# MODULE_WIFI_LAMP_CONTROL.net
KiCad netlist of a schematic drawn in Altium Designer
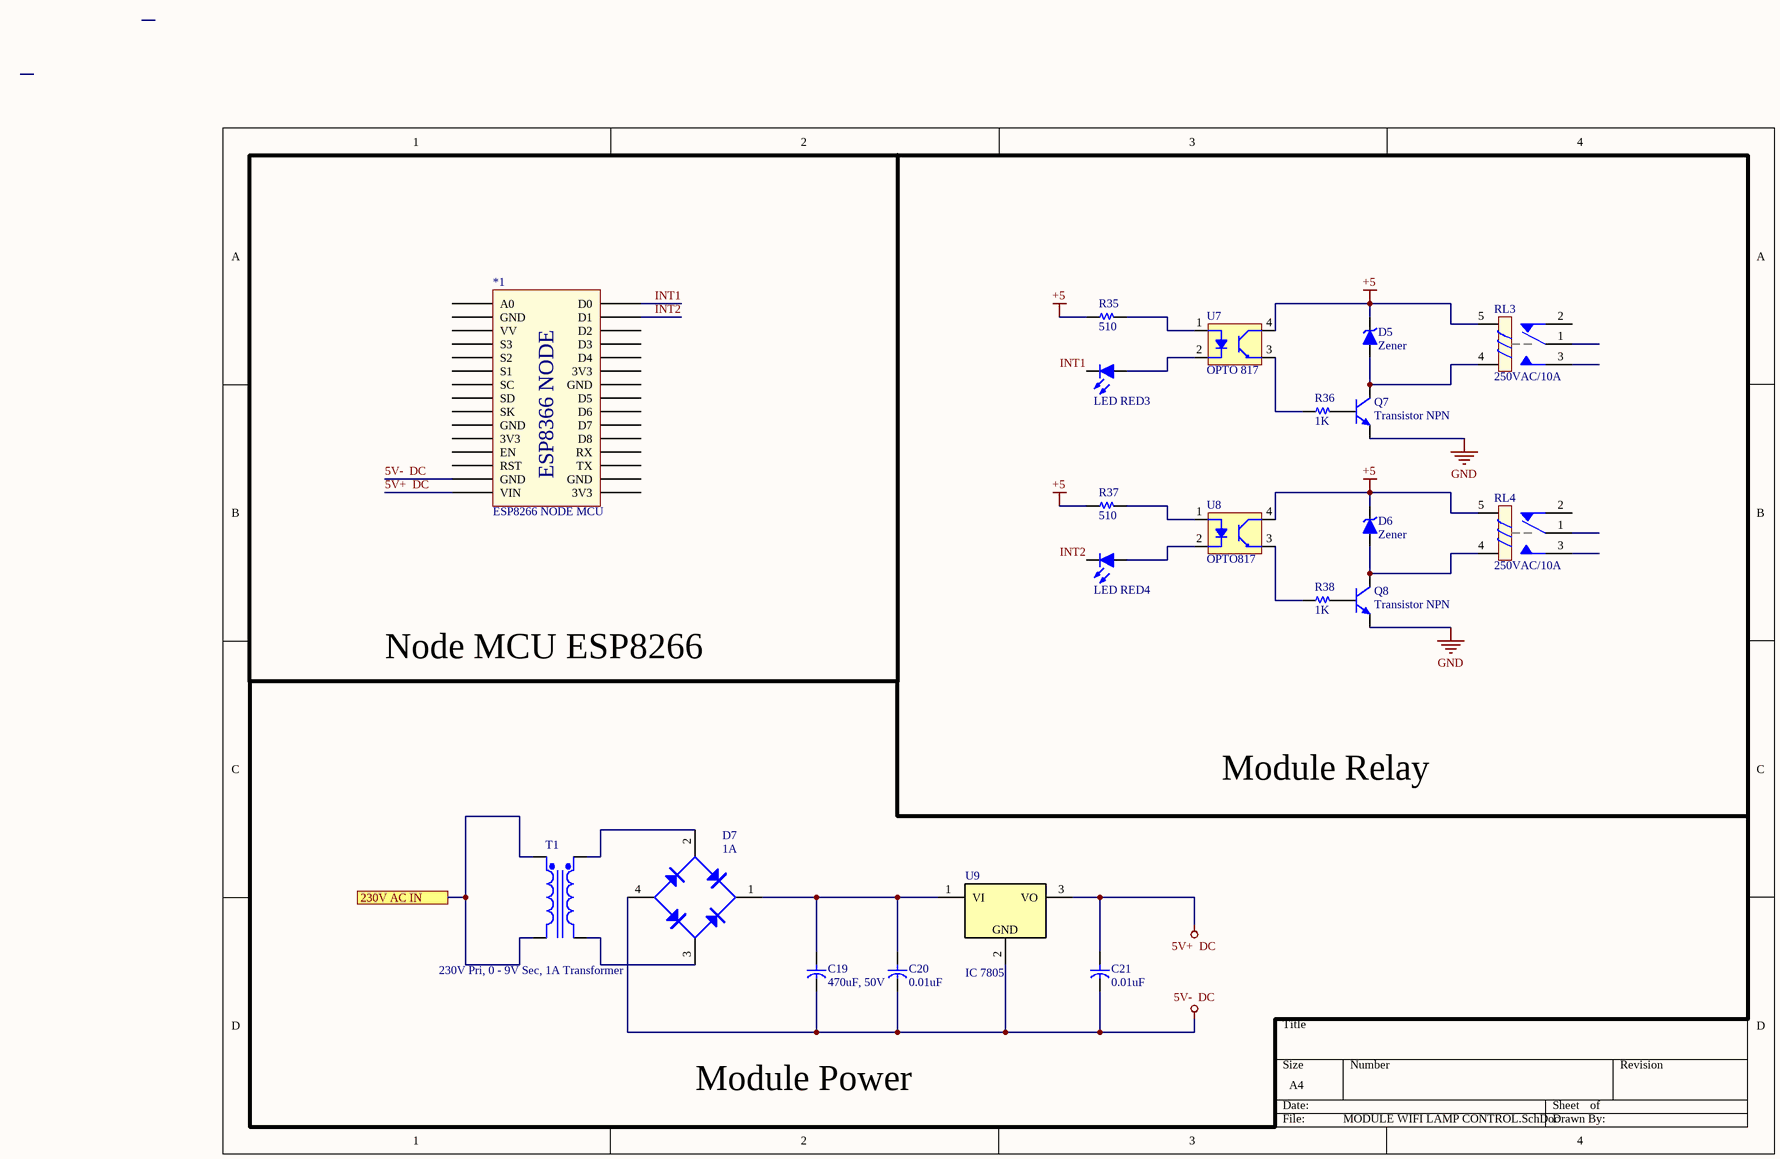
[diagram p0: MODULE WIFI LAMP CONTROL.SchDoc]

(export (version "E")
  (design (tool "Eeschema 10.0.6"))
  (components
    (comp (ref "*1")
      (value "ESP8266 NODE MCU")
      (footprint "ESP8266 NODE MCU")
      (libsource (lib "Altium_Lib_by_KhueNguyenCreator") (part "ESP8266 NODE MCU"))
    )
    (comp (ref "C19")
      (value "470uF, 50V")
      (footprint "CYL/D.500/LS.200")
      (description "Capacitor pol")
      (libsource (lib "chipfc_altium_libs") (part "Capacitor"))
    )
    (comp (ref "C20")
      (value "0.01uF")
      (footprint "CYL/D.500/LS.200")
      (description "Capacitor pol")
      (libsource (lib "chipfc_altium_libs") (part "Capacitor"))
    )
    (comp (ref "C21")
      (value "0.01uF")
      (footprint "CYL/D.500/LS.200")
      (description "Capacitor pol")
      (libsource (lib "chipfc_altium_libs") (part "Capacitor"))
    )
    (comp (ref "D5")
      (value "Zener")
      (footprint "DO-41")
      (description "Zener Diode")
      (libsource (lib "chipfc_altium_libs") (part "Diode Zener"))
    )
    (comp (ref "D6")
      (value "Zener")
      (footprint "DO-41")
      (description "Zener Diode")
      (libsource (lib "chipfc_altium_libs") (part "Diode Zener"))
    )
    (comp (ref "D7")
      (value "1A")
      (footprint "BRIDGE_DAN")
      (description "Diode Bridge")
      (libsource (lib "Devzone_SCHLib") (part "BRIDGE1"))
    )
    (comp (ref "LED RED3")
      (value "LED RED")
      (footprint "LED 5MM - RED")
      (description "Typical LED")
      (libsource (lib "chipfc_altium_libs") (part "Led"))
    )
    (comp (ref "LED RED4")
      (value "LED RED")
      (footprint "LED 5MM - RED")
      (description "Typical LED")
      (libsource (lib "chipfc_altium_libs") (part "Led"))
    )
    (comp (ref "Q7")
      (value "Transistor NPN")
      (footprint "SOT-23")
      (description "NPN Bipolar Transistor")
      (libsource (lib "chipfc_altium_libs") (part "Transistor NPN"))
    )
    (comp (ref "Q8")
      (value "Transistor NPN")
      (footprint "SOT-23")
      (description "NPN Bipolar Transistor")
      (libsource (lib "chipfc_altium_libs") (part "Transistor NPN"))
    )
    (comp (ref "R35")
      (value "510")
      (footprint "R 1/4W/300")
      (description "Resistor")
      (libsource (lib "chipfc_altium_libs") (part "Resistor"))
    )
    (comp (ref "R36")
      (value "1K")
      (footprint "R 1/4W/300")
      (description "Resistor")
      (libsource (lib "chipfc_altium_libs") (part "Resistor"))
    )
    (comp (ref "R37")
      (value "510")
      (footprint "R 1/4W/300")
      (description "Resistor")
      (libsource (lib "chipfc_altium_libs") (part "Resistor"))
    )
    (comp (ref "R38")
      (value "1K")
      (footprint "R 1/4W/300")
      (description "Resistor")
      (libsource (lib "chipfc_altium_libs") (part "Resistor"))
    )
    (comp (ref "RL3")
      (value "250VAC/10A")
      (footprint "Relay 5 Chan SRD")
      (description "Relay 5 Chan")
      (libsource (lib "Altium_Lib_by_KhueNguyenCreator") (part "Relay 5 Chan SRD"))
    )
    (comp (ref "RL4")
      (value "250VAC/10A")
      (footprint "Relay 5 Chan SRD")
      (description "Relay 5 Chan")
      (libsource (lib "Altium_Lib_by_KhueNguyenCreator") (part "Relay 5 Chan SRD"))
    )
    (comp (ref "T1")
      (value "230V Pri, 0 - 9V Sec, 1A Transformer")
      (footprint "TRF_4")
      (description "Transformer (Coupled Inductor Model)")
      (fields (field (name "PUBLISHER") "Altium Limited"))
      (libsource (lib "SCH_MyLib_0") (part "Trans Cupl"))
    )
    (comp (ref "U7")
      (value "OPTO 817")
      (footprint "DIP4 - PC817")
      (description "Opto PC817B")
      (libsource (lib "chipfc_altium_libs") (part "PC817"))
    )
    (comp (ref "U8")
      (value "OPTO817")
      (footprint "DIP4 - PC817")
      (description "Opto PC817B")
      (libsource (lib "chipfc_altium_libs") (part "PC817"))
    )
    (comp (ref "U9")
      (value "IC 7805")
      (footprint "DPAK_118_446_112X59_SMD")
      (description "Linear Voltage Regulator IC 1 Output 1.5A DPAK")
      (fields (field (name "MANUFACTURER") "Diodes") (field (name "MANUFACTURER PART NUMBER") "L7805CDT-TR"))
      (libsource (lib "Altium_Lib_by_KhueNguyenCreator") (part "REG_35V_5V-1.5A-7.5W-DPAK"))
    )
  )
  (nets
    (net (code "1") (name "+5") (class "Default")
      (node (ref "D5") (pin "2") (pinfunction "K_2") (pintype "passive"))
      (node (ref "D6") (pin "2") (pinfunction "K_2") (pintype "passive"))
      (node (ref "R35") (pin "1") (pinfunction "1_1") (pintype "passive"))
      (node (ref "R37") (pin "1") (pinfunction "1_1") (pintype "passive"))
      (node (ref "RL3") (pin "5") (pinfunction "5_5") (pintype "passive"))
      (node (ref "RL4") (pin "5") (pinfunction "5_5") (pintype "passive"))
      (node (ref "U7") (pin "4") (pinfunction "C_4") (pintype "passive"))
      (node (ref "U8") (pin "4") (pinfunction "C_4") (pintype "passive"))
    )
    (net (code "2") (name "/230V AC IN") (class "Default")
      (node (ref "T1") (pin "1") (pinfunction "Pri+_1") (pintype "passive"))
      (node (ref "T1") (pin "2") (pinfunction "Pri-_2") (pintype "passive"))
    )
    (net (code "3") (name "/INT1") (class "Default")
      (node (ref "*1") (pin "30") (pinfunction "D0_30") (pintype "passive"))
    )
    (net (code "4") (name "/INT2") (class "Default")
      (node (ref "*1") (pin "29") (pinfunction "D1_29") (pintype "passive"))
    )
    (net (code "5") (name "5V+  DC") (class "Default")
      (node (ref "*1") (pin "15") (pinfunction "VIN_15") (pintype "passive"))
      (node (ref "C21") (pin "1") (pinfunction "1_1") (pintype "passive"))
      (node (ref "U9") (pin "3") (pinfunction "VO_3") (pintype "passive"))
    )
    (net (code "6") (name "5V-  DC") (class "Default")
      (node (ref "*1") (pin "14") (pinfunction "GND_14") (pintype "passive"))
      (node (ref "C19") (pin "2") (pinfunction "2_2") (pintype "passive"))
      (node (ref "C20") (pin "2") (pinfunction "2_2") (pintype "passive"))
      (node (ref "C21") (pin "2") (pinfunction "2_2") (pintype "passive"))
      (node (ref "D7") (pin "4") (pinfunction "V-_4") (pintype "passive"))
      (node (ref "U9") (pin "2") (pintype "passive"))
    )
    (net (code "7") (name "GND") (class "Default")
      (node (ref "Q7") (pin "2") (pinfunction "E_2") (pintype "passive"))
      (node (ref "Q8") (pin "2") (pinfunction "E_2") (pintype "passive"))
    )
    (net (code "8") (name "Net-(D5-A)") (class "Default")
      (node (ref "D5") (pin "1") (pinfunction "A_1") (pintype "passive"))
      (node (ref "Q7") (pin "3") (pinfunction "C_3") (pintype "passive"))
      (node (ref "RL3") (pin "4") (pinfunction "4_4") (pintype "passive"))
    )
    (net (code "9") (name "Net-(D6-A)") (class "Default")
      (node (ref "D6") (pin "1") (pinfunction "A_1") (pintype "passive"))
      (node (ref "Q8") (pin "3") (pinfunction "C_3") (pintype "passive"))
      (node (ref "RL4") (pin "4") (pinfunction "4_4") (pintype "passive"))
    )
    (net (code "10") (name "Net-(D7-V+)") (class "Default")
      (node (ref "C19") (pin "1") (pinfunction "1_1") (pintype "passive"))
      (node (ref "C20") (pin "1") (pinfunction "1_1") (pintype "passive"))
      (node (ref "D7") (pin "1") (pinfunction "V+_1") (pintype "passive"))
      (node (ref "U9") (pin "1") (pinfunction "VI_1") (pintype "passive"))
    )
    (net (code "11") (name "Net-(LED RED3-A)") (class "Default")
      (node (ref "LED RED3") (pin "1") (pinfunction "A_1") (pintype "passive"))
      (node (ref "U7") (pin "2") (pinfunction "K_2") (pintype "passive"))
    )
    (net (code "12") (name "Net-(LED RED4-A)") (class "Default")
      (node (ref "LED RED4") (pin "1") (pinfunction "A_1") (pintype "passive"))
      (node (ref "U8") (pin "2") (pinfunction "K_2") (pintype "passive"))
    )
    (net (code "13") (name "Net-(Q7-B)") (class "Default")
      (node (ref "Q7") (pin "1") (pinfunction "B_1") (pintype "passive"))
      (node (ref "R36") (pin "2") (pinfunction "2_2") (pintype "passive"))
    )
    (net (code "14") (name "Net-(Q8-B)") (class "Default")
      (node (ref "Q8") (pin "1") (pinfunction "B_1") (pintype "passive"))
      (node (ref "R38") (pin "2") (pinfunction "2_2") (pintype "passive"))
    )
    (net (code "15") (name "Net-(T1-Sec+)") (class "Default")
      (node (ref "D7") (pin "2") (pinfunction "AC_2") (pintype "passive"))
      (node (ref "T1") (pin "3") (pinfunction "Sec+_3") (pintype "passive"))
    )
    (net (code "16") (name "Net-(T1-Sec-)") (class "Default")
      (node (ref "D7") (pin "3") (pinfunction "AC_3") (pintype "passive"))
      (node (ref "T1") (pin "4") (pinfunction "Sec-_4") (pintype "passive"))
    )
    (net (code "17") (name "Net-(U7-A)") (class "Default")
      (node (ref "R35") (pin "2") (pinfunction "2_2") (pintype "passive"))
      (node (ref "U7") (pin "1") (pinfunction "A_1") (pintype "passive"))
    )
    (net (code "18") (name "Net-(U7-E)") (class "Default")
      (node (ref "R36") (pin "1") (pinfunction "1_1") (pintype "passive"))
      (node (ref "U7") (pin "3") (pinfunction "E_3") (pintype "passive"))
    )
    (net (code "19") (name "Net-(U8-A)") (class "Default")
      (node (ref "R37") (pin "2") (pinfunction "2_2") (pintype "passive"))
      (node (ref "U8") (pin "1") (pinfunction "A_1") (pintype "passive"))
    )
    (net (code "20") (name "Net-(U8-E)") (class "Default")
      (node (ref "R38") (pin "1") (pinfunction "1_1") (pintype "passive"))
      (node (ref "U8") (pin "3") (pinfunction "E_3") (pintype "passive"))
    )
    (net (code "21") (name "unconnected-(*1-3V3-Pad11)") (class "Default")
      (node (ref "*1") (pin "11") (pinfunction "3V3_11") (pintype "passive"))
    )
    (net (code "22") (name "unconnected-(*1-3V3-Pad16)") (class "Default")
      (node (ref "*1") (pin "16") (pinfunction "3V3_16") (pintype "passive"))
    )
    (net (code "23") (name "unconnected-(*1-3V3-Pad25)") (class "Default")
      (node (ref "*1") (pin "25") (pinfunction "3V3_25") (pintype "passive"))
    )
    (net (code "24") (name "unconnected-(*1-A0-Pad1)") (class "Default")
      (node (ref "*1") (pin "1") (pinfunction "A0_1") (pintype "passive"))
    )
    (net (code "25") (name "unconnected-(*1-D2-Pad28)") (class "Default")
      (node (ref "*1") (pin "28") (pinfunction "D2_28") (pintype "passive"))
    )
    (net (code "26") (name "unconnected-(*1-D3-Pad27)") (class "Default")
      (node (ref "*1") (pin "27") (pinfunction "D3_27") (pintype "passive"))
    )
    (net (code "27") (name "unconnected-(*1-D4-Pad26)") (class "Default")
      (node (ref "*1") (pin "26") (pinfunction "D4_26") (pintype "passive"))
    )
    (net (code "28") (name "unconnected-(*1-D5-Pad23)") (class "Default")
      (node (ref "*1") (pin "23") (pinfunction "D5_23") (pintype "passive"))
    )
    (net (code "29") (name "unconnected-(*1-D6-Pad22)") (class "Default")
      (node (ref "*1") (pin "22") (pinfunction "D6_22") (pintype "passive"))
    )
    (net (code "30") (name "unconnected-(*1-D7-Pad21)") (class "Default")
      (node (ref "*1") (pin "21") (pinfunction "D7_21") (pintype "passive"))
    )
    (net (code "31") (name "unconnected-(*1-D8-Pad20)") (class "Default")
      (node (ref "*1") (pin "20") (pinfunction "D8_20") (pintype "passive"))
    )
    (net (code "32") (name "unconnected-(*1-EN-Pad12)") (class "Default")
      (node (ref "*1") (pin "12") (pinfunction "EN_12") (pintype "passive"))
    )
    (net (code "33") (name "unconnected-(*1-GND-Pad2)") (class "Default")
      (node (ref "*1") (pin "2") (pinfunction "GND_2") (pintype "passive"))
    )
    (net (code "34") (name "unconnected-(*1-GND-Pad10)") (class "Default")
      (node (ref "*1") (pin "10") (pinfunction "GND_10") (pintype "passive"))
    )
    (net (code "35") (name "unconnected-(*1-GND-Pad17)") (class "Default")
      (node (ref "*1") (pin "17") (pinfunction "GND_17") (pintype "passive"))
    )
    (net (code "36") (name "unconnected-(*1-GND-Pad24)") (class "Default")
      (node (ref "*1") (pin "24") (pinfunction "GND_24") (pintype "passive"))
    )
    (net (code "37") (name "unconnected-(*1-RST-Pad13)") (class "Default")
      (node (ref "*1") (pin "13") (pinfunction "RST_13") (pintype "passive"))
    )
    (net (code "38") (name "unconnected-(*1-RX-Pad19)") (class "Default")
      (node (ref "*1") (pin "19") (pinfunction "RX_19") (pintype "passive"))
    )
    (net (code "39") (name "unconnected-(*1-S1-Pad6)") (class "Default")
      (node (ref "*1") (pin "6") (pinfunction "S1_6") (pintype "passive"))
    )
    (net (code "40") (name "unconnected-(*1-S2-Pad5)") (class "Default")
      (node (ref "*1") (pin "5") (pinfunction "S2_5") (pintype "passive"))
    )
    (net (code "41") (name "unconnected-(*1-S3-Pad4)") (class "Default")
      (node (ref "*1") (pin "4") (pinfunction "S3_4") (pintype "passive"))
    )
    (net (code "42") (name "unconnected-(*1-SC-Pad7)") (class "Default")
      (node (ref "*1") (pin "7") (pinfunction "SC_7") (pintype "passive"))
    )
    (net (code "43") (name "unconnected-(*1-SD-Pad8)") (class "Default")
      (node (ref "*1") (pin "8") (pinfunction "SD_8") (pintype "passive"))
    )
    (net (code "44") (name "unconnected-(*1-SK-Pad9)") (class "Default")
      (node (ref "*1") (pin "9") (pinfunction "SK_9") (pintype "passive"))
    )
    (net (code "45") (name "unconnected-(*1-TX-Pad18)") (class "Default")
      (node (ref "*1") (pin "18") (pinfunction "TX_18") (pintype "passive"))
    )
    (net (code "46") (name "unconnected-(*1-VV-Pad3)") (class "Default")
      (node (ref "*1") (pin "3") (pinfunction "VV_3") (pintype "passive"))
    )
    (net (code "47") (name "unconnected-(LED RED3-K-Pad2)") (class "Default")
      (node (ref "LED RED3") (pin "2") (pinfunction "K_2") (pintype "passive"))
    )
    (net (code "48") (name "unconnected-(LED RED4-K-Pad2)") (class "Default")
      (node (ref "LED RED4") (pin "2") (pinfunction "K_2") (pintype "passive"))
    )
    (net (code "49") (name "unconnected-(RL3-Pad1)") (class "Default")
      (node (ref "RL3") (pin "1") (pinfunction "1_1") (pintype "passive"))
    )
    (net (code "50") (name "unconnected-(RL3-Pad2)") (class "Default")
      (node (ref "RL3") (pin "2") (pinfunction "2_2") (pintype "passive"))
    )
    (net (code "51") (name "unconnected-(RL3-Pad3)") (class "Default")
      (node (ref "RL3") (pin "3") (pinfunction "3_3") (pintype "passive"))
    )
    (net (code "52") (name "unconnected-(RL4-Pad1)") (class "Default")
      (node (ref "RL4") (pin "1") (pinfunction "1_1") (pintype "passive"))
    )
    (net (code "53") (name "unconnected-(RL4-Pad2)") (class "Default")
      (node (ref "RL4") (pin "2") (pinfunction "2_2") (pintype "passive"))
    )
    (net (code "54") (name "unconnected-(RL4-Pad3)") (class "Default")
      (node (ref "RL4") (pin "3") (pinfunction "3_3") (pintype "passive"))
    )
  )
)
